# TEMP.net
KiCad netlist of a schematic drawn in Altium Designer
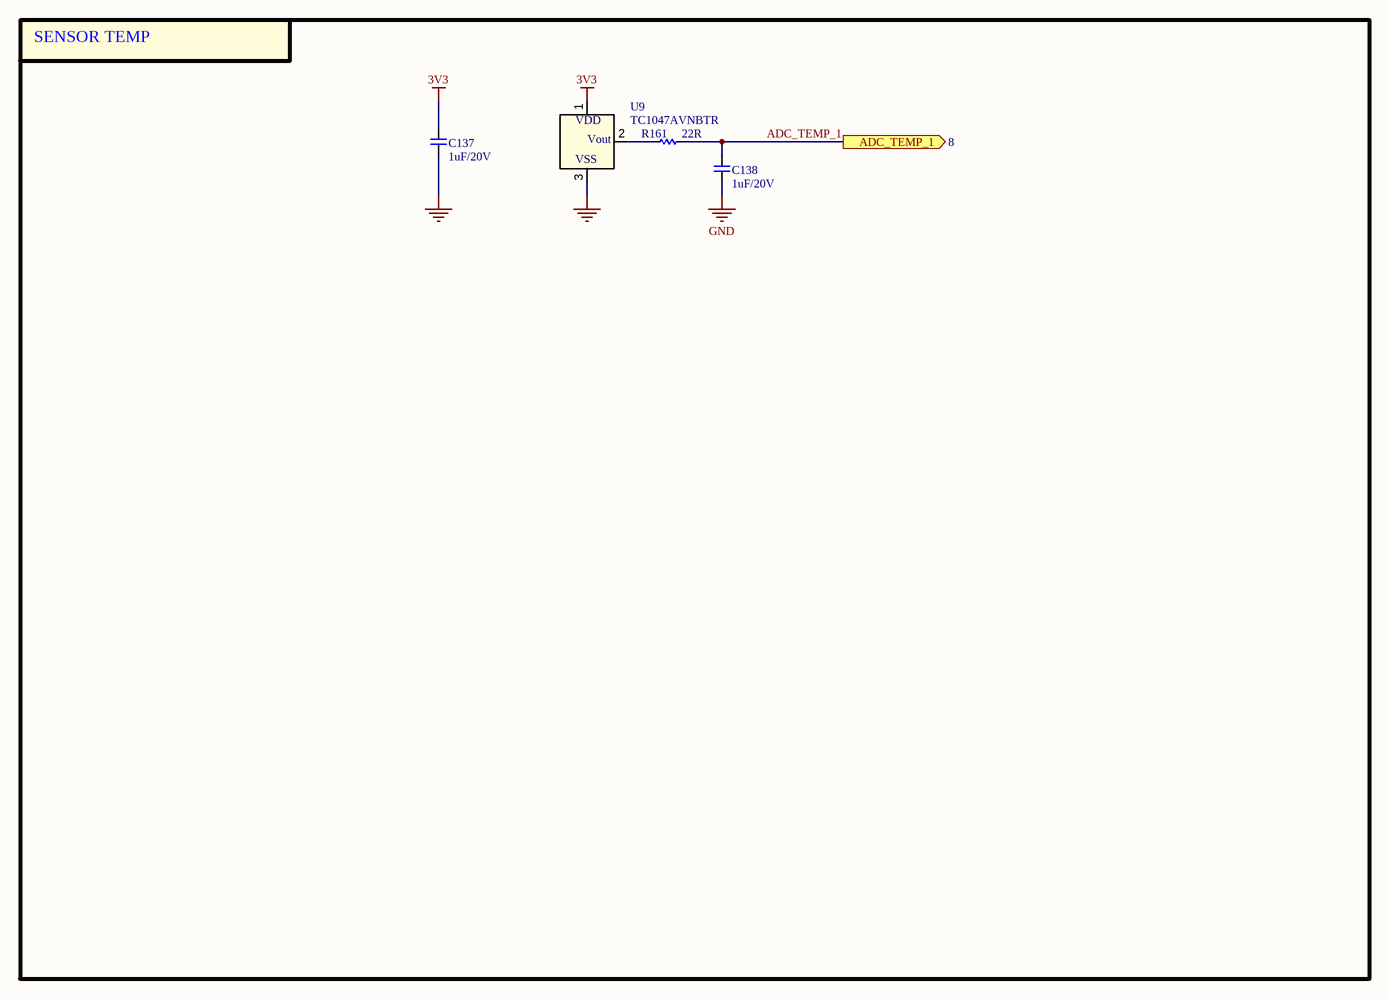
[diagram p0: TEMP.SchDoc]

(export (version "E")
  (design (tool "Eeschema 10.0.6"))
  (components
    (comp (ref "C137")
      (value "1uF/20V")
      (footprint "CAP_C_1005X50_L")
      (description "CAP CHIP")
      (libsource (lib "IFBschelib") (part "_CAP_C_2"))
    )
    (comp (ref "C138")
      (value "1uF/20V")
      (footprint "CAP_C_1005X50_L")
      (description "CAP CHIP")
      (libsource (lib "IFBschelib") (part "_CAP_C_2"))
    )
    (comp (ref "R161")
      (value "22R")
      (footprint "RES_C_1005x30_L")
      (description "RES")
      (libsource (lib "IFBschelib") (part "_RES_B_2"))
    )
    (comp (ref "U9")
      (value "TC1047AVNBTR")
      (footprint "SOT-23_MC_MCH")
      (description "SENSOR ANALOG -40C-125C SOT23-3")
      (fields (field (name "COPYRIGHT") "Copyright (C) 2025 Ultra Librarian. All rights reserved."))
      (libsource (lib "IFBschelib") (part "TC1047AVNBTR"))
    )
  )
  (nets
    (net (code "1") (name "/ADC_TEMP_1") (class "Default")
      (node (ref "C138") (pin "2") (pinfunction "2_2") (pintype "passive"))
      (node (ref "R161") (pin "2") (pinfunction "2_2") (pintype "passive"))
    )
    (net (code "2") (name "3V3") (class "Default")
      (node (ref "C137") (pin "2") (pinfunction "2_2") (pintype "passive"))
      (node (ref "U9") (pin "1") (pinfunction "VDD_1") (pintype "passive"))
    )
    (net (code "3") (name "GND") (class "Default")
      (node (ref "C137") (pin "1") (pinfunction "1_1") (pintype "passive"))
      (node (ref "C138") (pin "1") (pinfunction "1_1") (pintype "passive"))
      (node (ref "U9") (pin "3") (pinfunction "VSS_3") (pintype "passive"))
    )
    (net (code "4") (name "Net-(U9-VOUT)") (class "Default")
      (node (ref "R161") (pin "1") (pinfunction "1_1") (pintype "passive"))
      (node (ref "U9") (pin "2") (pinfunction "VOUT_2") (pintype "passive"))
    )
  )
)
